# tello-charger.net
KiCad netlist of a schematic drawn in EAGLE
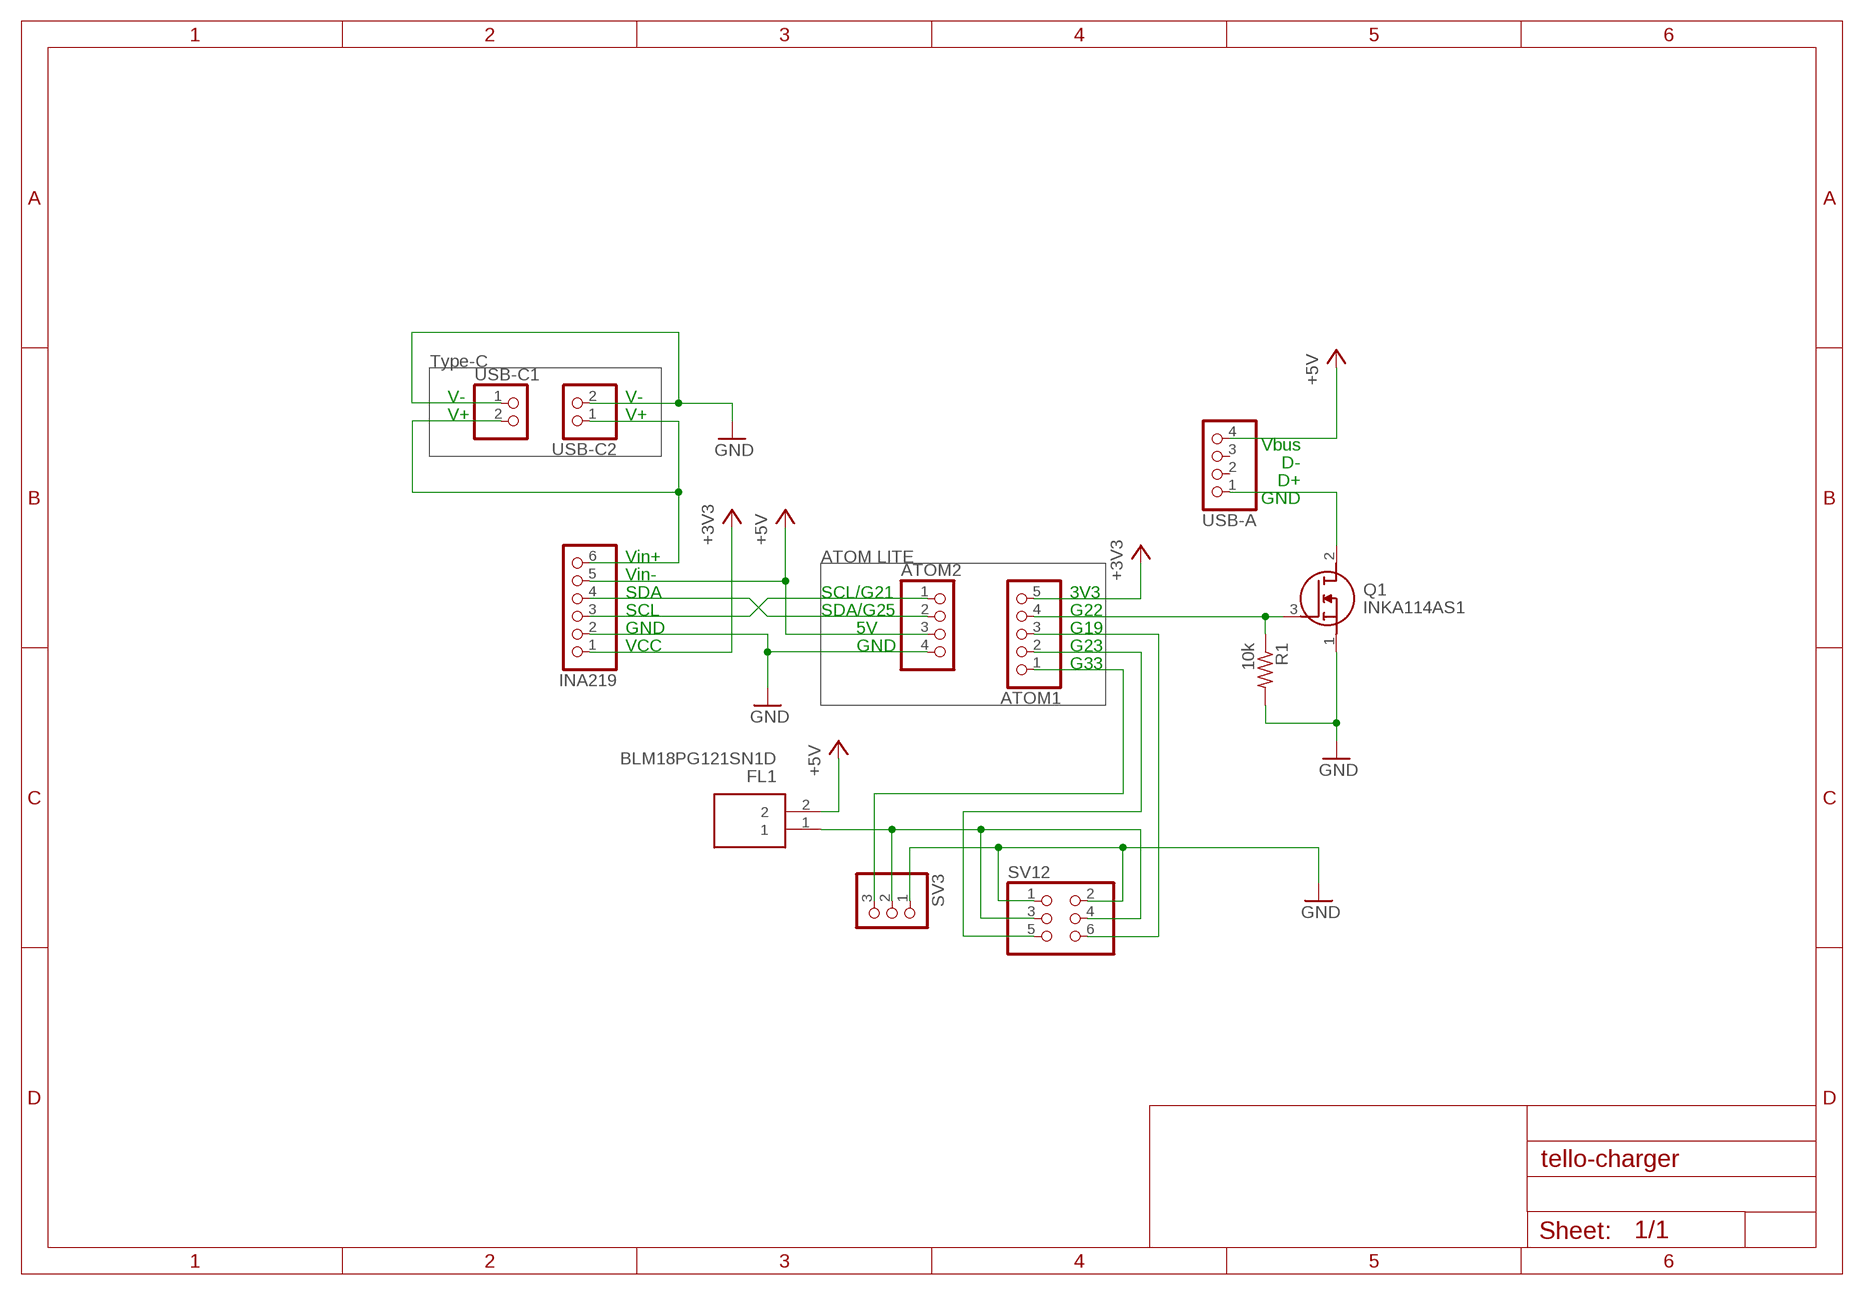
[diagram p0: schematic, sheet 1]

(export (version "E")
  (design (tool "Eeschema 10.0.6"))
  (components
    (comp (ref "ATOM1")
      (value "PINHD-1X5")
      (footprint "eagle-import:1X05")
      (libsource (lib "eagle-import") (part "PINHD-1X5"))
    )
    (comp (ref "ATOM2")
      (value "PINHD-1X4")
      (footprint "eagle-import:1X04")
      (libsource (lib "eagle-import") (part "PINHD-1X4"))
    )
    (comp (ref "FL1")
      (value "BLM18PG121SN1D")
      (footprint "eagle-import:BLM18AG102BH1D")
      (fields (field (name "MOUSER_PART_NUMBER") "81-BLM18PG121SN1D"))
      (libsource (lib "eagle-import") (part "BLM18PG121SN1D"))
    )
    (comp (ref "INA219")
      (value "PINHD-1X6")
      (footprint "eagle-import:1X06")
      (libsource (lib "eagle-import") (part "PINHD-1X6"))
    )
    (comp (ref "Q1")
      (value "INKA114AS1")
      (footprint "eagle-import:INKA114AS1")
      (libsource (lib "eagle-import") (part "INKA114AS1"))
    )
    (comp (ref "R1")
      (value "10k")
      (footprint "eagle-import:R0603")
      (libsource (lib "eagle-import") (part "R-US_R0603"))
    )
    (comp (ref "SV3")
      (value "PINHD-1X3/90")
      (footprint "eagle-import:1X03_90")
      (libsource (lib "eagle-import") (part "PINHD-1X3/90"))
    )
    (comp (ref "SV12")
      (value "PINHD-2X3/90")
      (footprint "eagle-import:2X03_90")
      (libsource (lib "eagle-import") (part "PINHD-2X3/90"))
    )
    (comp (ref "USB-A")
      (value "PINHD-1X4")
      (footprint "eagle-import:1X04")
      (libsource (lib "eagle-import") (part "PINHD-1X4"))
    )
    (comp (ref "USB-C1")
      (value "PINHD-1X2")
      (footprint "eagle-import:1X02")
      (libsource (lib "eagle-import") (part "PINHD-1X2"))
    )
    (comp (ref "USB-C2")
      (value "PINHD-1X2")
      (footprint "eagle-import:1X02")
      (libsource (lib "eagle-import") (part "PINHD-1X2"))
    )
  )
  (nets
    (net (code "1") (name "+3V3") (class "Default")
      (node (ref "ATOM1") (pin "5") (pinfunction "5_5") (pintype "passive"))
      (node (ref "INA219") (pin "1") (pinfunction "1_1") (pintype "passive"))
    )
    (net (code "2") (name "+5V") (class "Default")
      (node (ref "ATOM2") (pin "3") (pinfunction "3_3") (pintype "passive"))
      (node (ref "FL1") (pin "2") (pinfunction "2_2") (pintype "bidirectional"))
      (node (ref "INA219") (pin "5") (pinfunction "5_5") (pintype "passive"))
      (node (ref "USB-A") (pin "4") (pinfunction "4_4") (pintype "passive"))
    )
    (net (code "3") (name "GND") (class "Default")
      (node (ref "ATOM2") (pin "4") (pinfunction "4_4") (pintype "passive"))
      (node (ref "INA219") (pin "2") (pinfunction "2_2") (pintype "passive"))
      (node (ref "Q1") (pin "1") (pinfunction "S_1") (pintype "bidirectional"))
      (node (ref "R1") (pin "2") (pinfunction "2_2") (pintype "passive"))
      (node (ref "SV12") (pin "1") (pinfunction "1_1") (pintype "passive"))
      (node (ref "SV12") (pin "2") (pinfunction "2_2") (pintype "passive"))
      (node (ref "SV3") (pin "1") (pinfunction "1_1") (pintype "passive"))
      (node (ref "USB-C1") (pin "1") (pinfunction "1_1") (pintype "passive"))
      (node (ref "USB-C2") (pin "2") (pinfunction "2_2") (pintype "passive"))
    )
    (net (code "4") (name "Net-(ATOM1-Pad1)") (class "Default")
      (node (ref "ATOM1") (pin "1") (pinfunction "1_1") (pintype "passive"))
      (node (ref "SV3") (pin "3") (pinfunction "3_3") (pintype "passive"))
    )
    (net (code "5") (name "Net-(ATOM1-Pad2)") (class "Default")
      (node (ref "ATOM1") (pin "2") (pinfunction "2_2") (pintype "passive"))
      (node (ref "SV12") (pin "5") (pinfunction "5_5") (pintype "passive"))
    )
    (net (code "6") (name "Net-(ATOM1-Pad3)") (class "Default")
      (node (ref "ATOM1") (pin "3") (pinfunction "3_3") (pintype "passive"))
      (node (ref "SV12") (pin "6") (pinfunction "6_6") (pintype "passive"))
    )
    (net (code "7") (name "Net-(ATOM2-Pad1)") (class "Default")
      (node (ref "ATOM2") (pin "1") (pinfunction "1_1") (pintype "passive"))
      (node (ref "INA219") (pin "3") (pinfunction "3_3") (pintype "passive"))
    )
    (net (code "8") (name "Net-(ATOM2-Pad2)") (class "Default")
      (node (ref "ATOM2") (pin "2") (pinfunction "2_2") (pintype "passive"))
      (node (ref "INA219") (pin "4") (pinfunction "4_4") (pintype "passive"))
    )
    (net (code "9") (name "Net-(FL1-Pad1)") (class "Default")
      (node (ref "FL1") (pin "1") (pinfunction "1_1") (pintype "bidirectional"))
      (node (ref "SV12") (pin "3") (pinfunction "3_3") (pintype "passive"))
      (node (ref "SV12") (pin "4") (pinfunction "4_4") (pintype "passive"))
      (node (ref "SV3") (pin "2") (pinfunction "2_2") (pintype "passive"))
    )
    (net (code "10") (name "Net-(INA219-Pad6)") (class "Default")
      (node (ref "INA219") (pin "6") (pinfunction "6_6") (pintype "passive"))
      (node (ref "USB-C1") (pin "2") (pinfunction "2_2") (pintype "passive"))
      (node (ref "USB-C2") (pin "1") (pinfunction "1_1") (pintype "passive"))
    )
    (net (code "11") (name "Net-(Q1-D)") (class "Default")
      (node (ref "Q1") (pin "2") (pinfunction "D_2") (pintype "bidirectional"))
      (node (ref "USB-A") (pin "1") (pinfunction "1_1") (pintype "passive"))
    )
    (net (code "12") (name "Net-(Q1-G)") (class "Default")
      (node (ref "ATOM1") (pin "4") (pinfunction "4_4") (pintype "passive"))
      (node (ref "Q1") (pin "3") (pinfunction "G_3") (pintype "bidirectional"))
      (node (ref "R1") (pin "1") (pinfunction "1_1") (pintype "passive"))
    )
    (net (code "13") (name "unconnected-(USB-A-Pad2)") (class "Default")
      (node (ref "USB-A") (pin "2") (pinfunction "2_2") (pintype "passive"))
    )
    (net (code "14") (name "unconnected-(USB-A-Pad3)") (class "Default")
      (node (ref "USB-A") (pin "3") (pinfunction "3_3") (pintype "passive"))
    )
  )
)
